# sensors_board.net
KiCad netlist of a schematic drawn in EAGLE
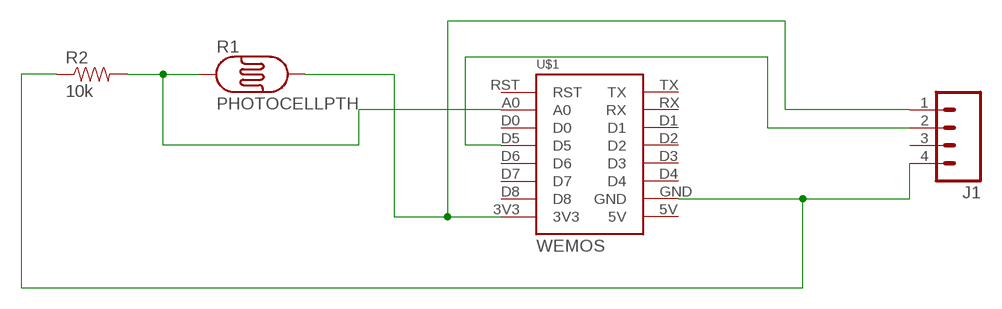
[diagram p0: schematic, sheet 1]

(export (version "E")
  (design (tool "Eeschema 10.0.6"))
  (components
    (comp (ref "J1")
      (value "M04PTH")
      (footprint "eagle-import:1X04")
      (libsource (lib "eagle-import") (part "M04PTH"))
    )
    (comp (ref "R1")
      (value "PHOTOCELLPTH")
      (footprint "eagle-import:PHOTOCELL")
      (libsource (lib "eagle-import") (part "PHOTOCELLPTH"))
    )
    (comp (ref "R2")
      (value "10k")
      (footprint "eagle-import:AXIAL-0.3")
      (libsource (lib "eagle-import") (part "10KOHM-1/4W-1%(PTH)HORIZ"))
    )
    (comp (ref "U$1")
      (value "WEMOS")
      (footprint "eagle-import:WEMOS")
      (libsource (lib "eagle-import") (part "WEMOS"))
    )
  )
  (nets
    (net (code "1") (name "Net-(J1-Pad2)") (class "Default")
      (node (ref "J1") (pin "2") (pinfunction "2_2") (pintype "passive"))
      (node (ref "U$1") (pin "D5") (pinfunction "D5_D5") (pintype "bidirectional"))
    )
    (net (code "2") (name "Net-(R1-P$1)") (class "Default")
      (node (ref "R1") (pin "1") (pinfunction "P$1_1") (pintype "bidirectional"))
      (node (ref "R2") (pin "P$2") (pinfunction "2_P$2") (pintype "passive"))
      (node (ref "U$1") (pin "A0") (pinfunction "A0_A0") (pintype "bidirectional"))
    )
    (net (code "3") (name "Net-(R1-P$2)") (class "Default")
      (node (ref "J1") (pin "1") (pinfunction "1_1") (pintype "passive"))
      (node (ref "R1") (pin "2") (pinfunction "P$2_2") (pintype "bidirectional"))
      (node (ref "U$1") (pin "3V3") (pinfunction "3V3_3V3") (pintype "bidirectional"))
    )
    (net (code "4") (name "Net-(R2-1)") (class "Default")
      (node (ref "J1") (pin "4") (pinfunction "4_4") (pintype "passive"))
      (node (ref "R2") (pin "P$1") (pinfunction "1_P$1") (pintype "passive"))
      (node (ref "U$1") (pin "GND") (pinfunction "GND_GND") (pintype "bidirectional"))
    )
    (net (code "5") (name "unconnected-(J1-Pad3)") (class "Default")
      (node (ref "J1") (pin "3") (pinfunction "3_3") (pintype "passive"))
    )
    (net (code "6") (name "unconnected-(U$1-Pad5V)") (class "Default")
      (node (ref "U$1") (pin "5V") (pinfunction "5V_5V") (pintype "bidirectional"))
    )
    (net (code "7") (name "unconnected-(U$1-PadD0)") (class "Default")
      (node (ref "U$1") (pin "D0") (pinfunction "D0_D0") (pintype "bidirectional"))
    )
    (net (code "8") (name "unconnected-(U$1-PadD1)") (class "Default")
      (node (ref "U$1") (pin "D1") (pinfunction "D1_D1") (pintype "bidirectional"))
    )
    (net (code "9") (name "unconnected-(U$1-PadD2)") (class "Default")
      (node (ref "U$1") (pin "D2") (pinfunction "D2_D2") (pintype "bidirectional"))
    )
    (net (code "10") (name "unconnected-(U$1-PadD3)") (class "Default")
      (node (ref "U$1") (pin "D3") (pinfunction "D3_D3") (pintype "bidirectional"))
    )
    (net (code "11") (name "unconnected-(U$1-PadD4)") (class "Default")
      (node (ref "U$1") (pin "D4") (pinfunction "D4_D4") (pintype "bidirectional"))
    )
    (net (code "12") (name "unconnected-(U$1-PadD6)") (class "Default")
      (node (ref "U$1") (pin "D6") (pinfunction "D6_D6") (pintype "bidirectional"))
    )
    (net (code "13") (name "unconnected-(U$1-PadD7)") (class "Default")
      (node (ref "U$1") (pin "D7") (pinfunction "D7_D7") (pintype "bidirectional"))
    )
    (net (code "14") (name "unconnected-(U$1-PadD8)") (class "Default")
      (node (ref "U$1") (pin "D8") (pinfunction "D8_D8") (pintype "bidirectional"))
    )
    (net (code "15") (name "unconnected-(U$1-PadRST)") (class "Default")
      (node (ref "U$1") (pin "RST") (pinfunction "RST_RST") (pintype "bidirectional"))
    )
    (net (code "16") (name "unconnected-(U$1-PadRX)") (class "Default")
      (node (ref "U$1") (pin "RX") (pinfunction "RX_RX") (pintype "bidirectional"))
    )
    (net (code "17") (name "unconnected-(U$1-PadTX)") (class "Default")
      (node (ref "U$1") (pin "TX") (pinfunction "TX_TX") (pintype "bidirectional"))
    )
  )
)
